# I2C-Trippe-sensor.net
KiCad netlist of a schematic drawn in EAGLE
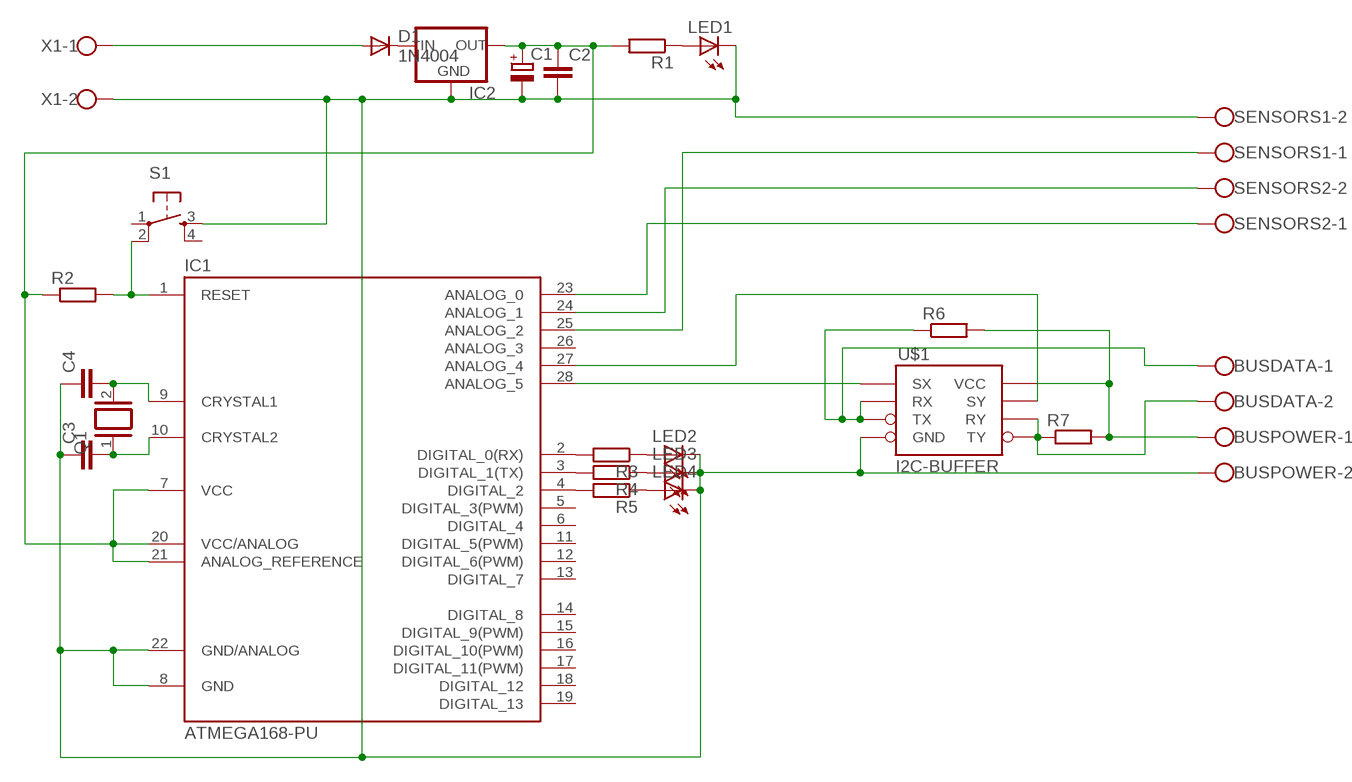
[diagram p0: schematic, sheet 1]

(export (version "E")
  (design (tool "Eeschema 10.0.6"))
  (components
    (comp (ref "BUSDATA")
      (value "W237-102")
      (footprint "eagle-import:W237-102")
      (fields (field (name "MPN") "237-102"))
      (libsource (lib "eagle-import") (part "W237-102"))
    )
    (comp (ref "BUSPOWER")
      (value "W237-102")
      (footprint "eagle-import:W237-102")
      (fields (field (name "MPN") "237-102"))
      (libsource (lib "eagle-import") (part "W237-102"))
    )
    (comp (ref "C1")
      (value "CPOL-EUE5-10.5")
      (footprint "eagle-import:E5-10,5")
      (libsource (lib "eagle-import") (part "CPOL-EUE5-10.5"))
    )
    (comp (ref "C2")
      (value "C-EU050-024X044")
      (footprint "eagle-import:C050-024X044")
      (libsource (lib "eagle-import") (part "resistor_C-EU050-024X044"))
    )
    (comp (ref "C3")
      (value "C-EU075-032X103")
      (footprint "eagle-import:C075-032X103")
      (libsource (lib "eagle-import") (part "C-EU075-032X103"))
    )
    (comp (ref "C4")
      (value "C-EU075-032X103")
      (footprint "eagle-import:C075-032X103")
      (libsource (lib "eagle-import") (part "C-EU075-032X103"))
    )
    (comp (ref "D1")
      (value "1N4004")
      (footprint "eagle-import:DO41-10")
      (libsource (lib "eagle-import") (part "1N4004"))
    )
    (comp (ref "IC1")
      (value "ATMEGA168-PU")
      (footprint "eagle-import:DIL28-3")
      (libsource (lib "eagle-import") (part "ATMEGA168-PU"))
    )
    (comp (ref "IC2")
      (value "78XXL")
      (footprint "eagle-import:78XXL")
      (libsource (lib "eagle-import") (part "78XXL"))
    )
    (comp (ref "LED1")
      (value "LED3MM")
      (footprint "eagle-import:LED3MM")
      (libsource (lib "eagle-import") (part "LED3MM"))
    )
    (comp (ref "LED2")
      (value "LED3MM")
      (footprint "eagle-import:LED3MM")
      (libsource (lib "eagle-import") (part "LED3MM"))
    )
    (comp (ref "LED3")
      (value "LED3MM")
      (footprint "eagle-import:LED3MM")
      (libsource (lib "eagle-import") (part "LED3MM"))
    )
    (comp (ref "LED4")
      (value "LED3MM")
      (footprint "eagle-import:LED3MM")
      (libsource (lib "eagle-import") (part "LED3MM"))
    )
    (comp (ref "Q1")
      (value "XTAL/S")
      (footprint "eagle-import:QS")
      (libsource (lib "eagle-import") (part "XTAL/S"))
    )
    (comp (ref "R1")
      (value "R-EU_0207/12")
      (footprint "eagle-import:0207_12")
      (libsource (lib "eagle-import") (part "R-EU_0207/12"))
    )
    (comp (ref "R2")
      (value "R-EU_0207/12")
      (footprint "eagle-import:0207_12")
      (libsource (lib "eagle-import") (part "R-EU_0207/12"))
    )
    (comp (ref "R3")
      (value "R-EU_0207/12")
      (footprint "eagle-import:0207_12")
      (libsource (lib "eagle-import") (part "R-EU_0207/12"))
    )
    (comp (ref "R4")
      (value "R-EU_0207/12")
      (footprint "eagle-import:0207_12")
      (libsource (lib "eagle-import") (part "R-EU_0207/12"))
    )
    (comp (ref "R5")
      (value "R-EU_0207/12")
      (footprint "eagle-import:0207_12")
      (libsource (lib "eagle-import") (part "R-EU_0207/12"))
    )
    (comp (ref "R6")
      (value "R-EU_0207/12")
      (footprint "eagle-import:0207_12")
      (libsource (lib "eagle-import") (part "R-EU_0207/12"))
    )
    (comp (ref "R7")
      (value "R-EU_0207/12")
      (footprint "eagle-import:0207_12")
      (libsource (lib "eagle-import") (part "R-EU_0207/12"))
    )
    (comp (ref "S1")
      (value "TAC_SWITCHPTH")
      (footprint "eagle-import:TACTILE-PTH")
      (libsource (lib "eagle-import") (part "TAC_SWITCHPTH"))
    )
    (comp (ref "SENSORS1")
      (value "W237-102")
      (footprint "eagle-import:W237-102")
      (fields (field (name "MPN") "237-102"))
      (libsource (lib "eagle-import") (part "W237-102"))
    )
    (comp (ref "SENSORS2")
      (value "W237-102")
      (footprint "eagle-import:W237-102")
      (fields (field (name "MPN") "237-102"))
      (libsource (lib "eagle-import") (part "W237-102"))
    )
    (comp (ref "U$1")
      (value "I2C-BUFFER")
      (footprint "eagle-import:I2C-BUFFER")
      (libsource (lib "eagle-import") (part "I2C-BUFFER"))
    )
    (comp (ref "X1")
      (value "W237-102")
      (footprint "eagle-import:W237-102")
      (fields (field (name "MPN") "237-102"))
      (libsource (lib "eagle-import") (part "W237-102"))
    )
  )
  (nets
    (net (code "1") (name "Net-(BUSDATAA-KL)") (class "Default")
      (node (ref "BUSDATA") (pin "1") (pinfunction "KL_1") (pintype "passive"))
      (node (ref "R6") (pin "1") (pinfunction "1_1") (pintype "passive"))
      (node (ref "U$1") (pin "2") (pinfunction "RX_2") (pintype "bidirectional"))
      (node (ref "U$1") (pin "3") (pinfunction "TX_3") (pintype "bidirectional"))
    )
    (net (code "2") (name "Net-(BUSDATAB-KL)") (class "Default")
      (node (ref "BUSDATA") (pin "2") (pinfunction "KL_2") (pintype "passive"))
      (node (ref "R7") (pin "1") (pinfunction "1_1") (pintype "passive"))
      (node (ref "U$1") (pin "5") (pinfunction "TY_5") (pintype "bidirectional"))
      (node (ref "U$1") (pin "6") (pinfunction "RY_6") (pintype "bidirectional"))
    )
    (net (code "3") (name "Net-(BUSPOWERA-KL)") (class "Default")
      (node (ref "BUSPOWER") (pin "1") (pinfunction "KL_1") (pintype "passive"))
      (node (ref "R6") (pin "2") (pinfunction "2_2") (pintype "passive"))
      (node (ref "R7") (pin "2") (pinfunction "2_2") (pintype "passive"))
      (node (ref "U$1") (pin "8") (pinfunction "VCC_8") (pintype "bidirectional"))
    )
    (net (code "4") (name "Net-(BUSPOWERB-KL)") (class "Default")
      (node (ref "BUSPOWER") (pin "2") (pinfunction "KL_2") (pintype "passive"))
      (node (ref "C1") (pin "-") (pinfunction "-_-") (pintype "passive"))
      (node (ref "C2") (pin "2") (pinfunction "2_2") (pintype "passive"))
      (node (ref "C3") (pin "1") (pinfunction "1_1") (pintype "passive"))
      (node (ref "C4") (pin "1") (pinfunction "1_1") (pintype "passive"))
      (node (ref "IC1") (pin "22") (pinfunction "GND/ANALOG_22") (pintype "power_in"))
      (node (ref "IC1") (pin "8") (pinfunction "GND_8") (pintype "power_in"))
      (node (ref "IC2") (pin "GND") (pinfunction "GND_GND") (pintype "input"))
      (node (ref "LED1") (pin "K") (pinfunction "C_K") (pintype "passive"))
      (node (ref "LED2") (pin "K") (pinfunction "C_K") (pintype "passive"))
      (node (ref "LED3") (pin "K") (pinfunction "C_K") (pintype "passive"))
      (node (ref "LED4") (pin "K") (pinfunction "C_K") (pintype "passive"))
      (node (ref "S1") (pin "3") (pinfunction "3_3") (pintype "passive"))
      (node (ref "SENSORS1") (pin "2") (pinfunction "KL_2") (pintype "passive"))
      (node (ref "U$1") (pin "4") (pinfunction "GND_4") (pintype "bidirectional"))
      (node (ref "X1") (pin "2") (pinfunction "KL_2") (pintype "passive"))
    )
    (net (code "5") (name "Net-(D1-PadC)") (class "Default")
      (node (ref "D1") (pin "C") (pinfunction "C_C") (pintype "passive"))
      (node (ref "IC2") (pin "IN") (pinfunction "IN_IN") (pintype "input"))
    )
    (net (code "6") (name "Net-(IC1-ANALOG_0)") (class "Default")
      (node (ref "IC1") (pin "23") (pinfunction "ANALOG_0_23") (pintype "bidirectional"))
      (node (ref "SENSORS2") (pin "1") (pinfunction "KL_1") (pintype "passive"))
    )
    (net (code "7") (name "Net-(IC1-ANALOG_1)") (class "Default")
      (node (ref "IC1") (pin "24") (pinfunction "ANALOG_1_24") (pintype "bidirectional"))
      (node (ref "SENSORS2") (pin "2") (pinfunction "KL_2") (pintype "passive"))
    )
    (net (code "8") (name "Net-(IC1-ANALOG_2)") (class "Default")
      (node (ref "IC1") (pin "25") (pinfunction "ANALOG_2_25") (pintype "bidirectional"))
      (node (ref "SENSORS1") (pin "1") (pinfunction "KL_1") (pintype "passive"))
    )
    (net (code "9") (name "Net-(IC1-ANALOG_4)") (class "Default")
      (node (ref "IC1") (pin "27") (pinfunction "ANALOG_4_27") (pintype "bidirectional"))
      (node (ref "U$1") (pin "7") (pinfunction "SY_7") (pintype "bidirectional"))
    )
    (net (code "10") (name "Net-(IC1-ANALOG_5)") (class "Default")
      (node (ref "IC1") (pin "28") (pinfunction "ANALOG_5_28") (pintype "bidirectional"))
      (node (ref "U$1") (pin "1") (pinfunction "SX_1") (pintype "bidirectional"))
    )
    (net (code "11") (name "Net-(IC1-ANALOG_REFERENCE)") (class "Default")
      (node (ref "C1") (pin "+") (pinfunction "+_+") (pintype "passive"))
      (node (ref "C2") (pin "1") (pinfunction "1_1") (pintype "passive"))
      (node (ref "IC1") (pin "20") (pinfunction "VCC/ANALOG_20") (pintype "passive"))
      (node (ref "IC1") (pin "21") (pinfunction "ANALOG_REFERENCE_21") (pintype "passive"))
      (node (ref "IC1") (pin "7") (pinfunction "VCC_7") (pintype "power_in"))
      (node (ref "IC2") (pin "OUT") (pinfunction "OUT_OUT") (pintype "passive"))
      (node (ref "R1") (pin "2") (pinfunction "2_2") (pintype "passive"))
      (node (ref "R2") (pin "1") (pinfunction "1_1") (pintype "passive"))
    )
    (net (code "12") (name "Net-(IC1-CRYSTAL1)") (class "Default")
      (node (ref "C4") (pin "2") (pinfunction "2_2") (pintype "passive"))
      (node (ref "IC1") (pin "9") (pinfunction "CRYSTAL1_9") (pintype "bidirectional"))
      (node (ref "Q1") (pin "2") (pinfunction "2_2") (pintype "passive"))
    )
    (net (code "13") (name "Net-(IC1-CRYSTAL2)") (class "Default")
      (node (ref "C3") (pin "2") (pinfunction "2_2") (pintype "passive"))
      (node (ref "IC1") (pin "10") (pinfunction "CRYSTAL2_10") (pintype "bidirectional"))
      (node (ref "Q1") (pin "1") (pinfunction "1_1") (pintype "passive"))
    )
    (net (code "14") (name "Net-(IC1-DIGITAL_0(RX))") (class "Default")
      (node (ref "IC1") (pin "2") (pinfunction "DIGITAL_0(RX)_2") (pintype "bidirectional"))
      (node (ref "R3") (pin "2") (pinfunction "2_2") (pintype "passive"))
    )
    (net (code "15") (name "Net-(IC1-DIGITAL_1(TX))") (class "Default")
      (node (ref "IC1") (pin "3") (pinfunction "DIGITAL_1(TX)_3") (pintype "bidirectional"))
      (node (ref "R4") (pin "2") (pinfunction "2_2") (pintype "passive"))
    )
    (net (code "16") (name "Net-(IC1-DIGITAL_2)") (class "Default")
      (node (ref "IC1") (pin "4") (pinfunction "DIGITAL_2_4") (pintype "bidirectional"))
      (node (ref "R5") (pin "2") (pinfunction "2_2") (pintype "passive"))
    )
    (net (code "17") (name "Net-(IC1-RESET)") (class "Default")
      (node (ref "IC1") (pin "1") (pinfunction "RESET_1") (pintype "bidirectional"))
      (node (ref "R2") (pin "2") (pinfunction "2_2") (pintype "passive"))
      (node (ref "S1") (pin "2") (pinfunction "2_2") (pintype "passive"))
    )
    (net (code "18") (name "Net-(LED1-PadA)") (class "Default")
      (node (ref "LED1") (pin "A") (pinfunction "A_A") (pintype "passive"))
      (node (ref "R1") (pin "1") (pinfunction "1_1") (pintype "passive"))
    )
    (net (code "19") (name "Net-(LED2-PadA)") (class "Default")
      (node (ref "LED2") (pin "A") (pinfunction "A_A") (pintype "passive"))
      (node (ref "R3") (pin "1") (pinfunction "1_1") (pintype "passive"))
    )
    (net (code "20") (name "Net-(LED3-PadA)") (class "Default")
      (node (ref "LED3") (pin "A") (pinfunction "A_A") (pintype "passive"))
      (node (ref "R4") (pin "1") (pinfunction "1_1") (pintype "passive"))
    )
    (net (code "21") (name "Net-(LED4-PadA)") (class "Default")
      (node (ref "LED4") (pin "A") (pinfunction "A_A") (pintype "passive"))
      (node (ref "R5") (pin "1") (pinfunction "1_1") (pintype "passive"))
    )
    (net (code "22") (name "Net-(X1A-KL)") (class "Default")
      (node (ref "D1") (pin "A") (pinfunction "A_A") (pintype "passive"))
      (node (ref "X1") (pin "1") (pinfunction "KL_1") (pintype "passive"))
    )
    (net (code "23") (name "unconnected-(IC1-ANALOG_3-Pad26)") (class "Default")
      (node (ref "IC1") (pin "26") (pinfunction "ANALOG_3_26") (pintype "bidirectional"))
    )
    (net (code "24") (name "unconnected-(IC1-DIGITAL_3(PWM)-Pad5)") (class "Default")
      (node (ref "IC1") (pin "5") (pinfunction "DIGITAL_3(PWM)_5") (pintype "bidirectional"))
    )
    (net (code "25") (name "unconnected-(IC1-DIGITAL_4-Pad6)") (class "Default")
      (node (ref "IC1") (pin "6") (pinfunction "DIGITAL_4_6") (pintype "bidirectional"))
    )
    (net (code "26") (name "unconnected-(IC1-DIGITAL_5(PWM)-Pad11)") (class "Default")
      (node (ref "IC1") (pin "11") (pinfunction "DIGITAL_5(PWM)_11") (pintype "bidirectional"))
    )
    (net (code "27") (name "unconnected-(IC1-DIGITAL_6(PWM)-Pad12)") (class "Default")
      (node (ref "IC1") (pin "12") (pinfunction "DIGITAL_6(PWM)_12") (pintype "bidirectional"))
    )
    (net (code "28") (name "unconnected-(IC1-DIGITAL_7-Pad13)") (class "Default")
      (node (ref "IC1") (pin "13") (pinfunction "DIGITAL_7_13") (pintype "bidirectional"))
    )
    (net (code "29") (name "unconnected-(IC1-DIGITAL_8-Pad14)") (class "Default")
      (node (ref "IC1") (pin "14") (pinfunction "DIGITAL_8_14") (pintype "bidirectional"))
    )
    (net (code "30") (name "unconnected-(IC1-DIGITAL_9(PWM)-Pad15)") (class "Default")
      (node (ref "IC1") (pin "15") (pinfunction "DIGITAL_9(PWM)_15") (pintype "bidirectional"))
    )
    (net (code "31") (name "unconnected-(IC1-DIGITAL_10(PWM)-Pad16)") (class "Default")
      (node (ref "IC1") (pin "16") (pinfunction "DIGITAL_10(PWM)_16") (pintype "bidirectional"))
    )
    (net (code "32") (name "unconnected-(IC1-DIGITAL_11(PWM)-Pad17)") (class "Default")
      (node (ref "IC1") (pin "17") (pinfunction "DIGITAL_11(PWM)_17") (pintype "bidirectional"))
    )
    (net (code "33") (name "unconnected-(IC1-DIGITAL_12-Pad18)") (class "Default")
      (node (ref "IC1") (pin "18") (pinfunction "DIGITAL_12_18") (pintype "bidirectional"))
    )
    (net (code "34") (name "unconnected-(IC1-DIGITAL_13-Pad19)") (class "Default")
      (node (ref "IC1") (pin "19") (pinfunction "DIGITAL_13_19") (pintype "bidirectional"))
    )
    (net (code "35") (name "unconnected-(S1-Pad1)") (class "Default")
      (node (ref "S1") (pin "1") (pinfunction "1_1") (pintype "passive"))
    )
    (net (code "36") (name "unconnected-(S1-Pad4)") (class "Default")
      (node (ref "S1") (pin "4") (pinfunction "4_4") (pintype "passive"))
    )
  )
)
